# TXPAFV2.net
KiCad netlist of a schematic drawn in Altium Designer
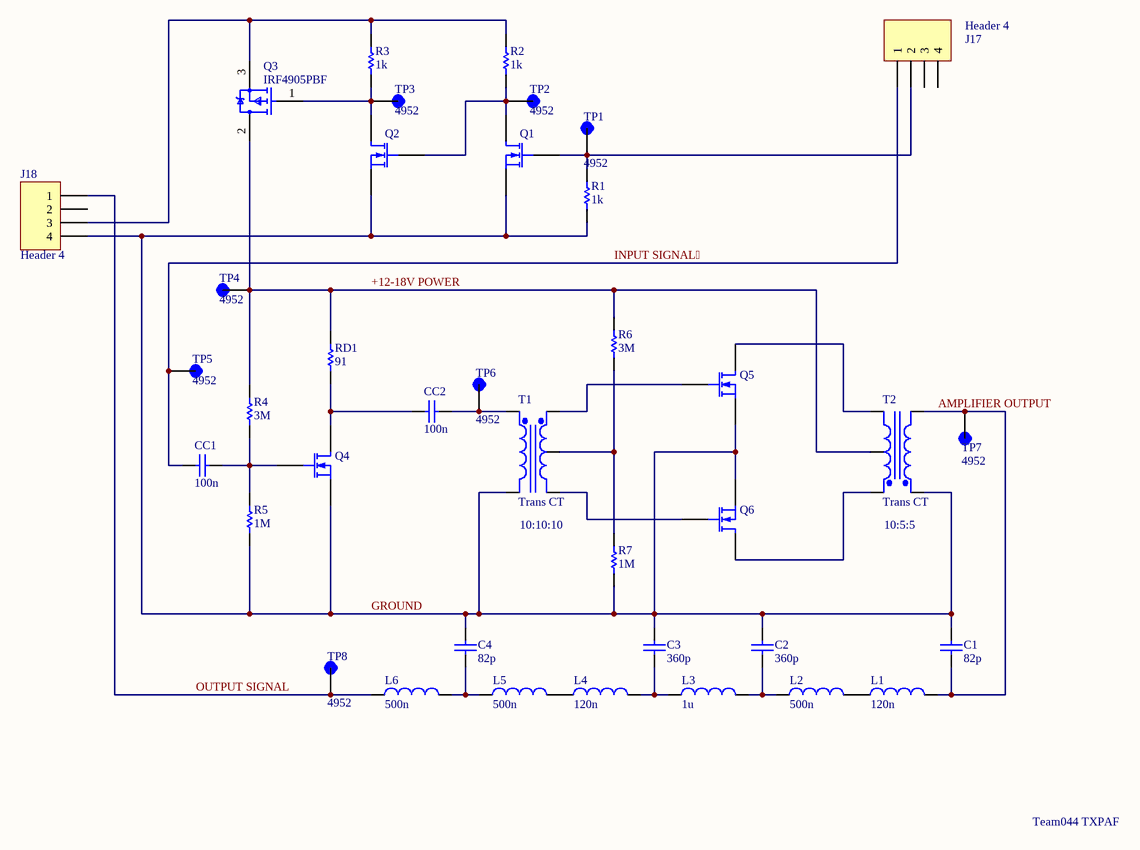
[diagram p0: TXPAFV2.SchDoc]

(export (version "E")
  (design (tool "Eeschema 10.0.6"))
  (components
    (comp (ref "C1")
      (value "82p")
      (footprint "K820J15C0GF5TL2")
      (description "Capacitor")
      (libsource (lib "Simulation Generic Components") (part "Capacitor"))
    )
    (comp (ref "C2")
      (value "360p")
      (footprint "C322C361J5G5TA")
      (description "Capacitor")
      (libsource (lib "Simulation Generic Components") (part "Capacitor"))
    )
    (comp (ref "C3")
      (value "360p")
      (footprint "C322C361J5G5TA")
      (description "Capacitor")
      (libsource (lib "Simulation Generic Components") (part "Capacitor"))
    )
    (comp (ref "C4")
      (value "82p")
      (footprint "K820J15C0GF5TL2")
      (description "Capacitor")
      (libsource (lib "Simulation Generic Components") (part "Capacitor"))
    )
    (comp (ref "CC1")
      (value "100n")
      (footprint "K104K15X7RF5TL2")
      (description "Capacitor")
      (libsource (lib "Simulation Generic Components") (part "Capacitor"))
    )
    (comp (ref "CC2")
      (value "100n")
      (footprint "K104K15X7RF5TL2")
      (description "Capacitor")
      (libsource (lib "Simulation Generic Components") (part "Capacitor"))
    )
    (comp (ref "J17")
      (value "Header 4")
      (footprint "HDR1X4")
      (description "Header, 4-Pin")
      (fields (field (name "PUBLISHER") "Altium Limited"))
      (libsource (lib "") (part "Header 4_1"))
    )
    (comp (ref "J18")
      (value "Header 4")
      (footprint "HDR1X4")
      (description "Header, 4-Pin")
      (fields (field (name "PUBLISHER") "Altium Limited"))
      (libsource (lib "Miscellaneous Connectors") (part "Header 4"))
    )
    (comp (ref "L1")
      (value "120n")
      (footprint "9230-96-RC")
      (description "Inductor")
      (libsource (lib "Simulation Generic Components") (part "Inductor"))
    )
    (comp (ref "L2")
      (value "500n")
      (footprint "78432010005")
      (description "Inductor")
      (libsource (lib "Simulation Generic Components") (part "Inductor"))
    )
    (comp (ref "L3")
      (value "1u")
      (footprint "9250A-102-RC")
      (description "Inductor")
      (libsource (lib "Simulation Generic Components") (part "Inductor"))
    )
    (comp (ref "L4")
      (value "120n")
      (footprint "9230-96-RC")
      (description "Inductor")
      (libsource (lib "Simulation Generic Components") (part "Inductor"))
    )
    (comp (ref "L5")
      (value "500n")
      (footprint "78432010005")
      (description "Inductor")
      (libsource (lib "Simulation Generic Components") (part "Inductor"))
    )
    (comp (ref "L6")
      (value "500n")
      (footprint "78432010005")
      (description "Inductor")
      (libsource (lib "Simulation Generic Components") (part "Inductor"))
    )
    (comp (ref "Q1")
      (value "N-chanel Power MOSFET VDMOS Model")
      (footprint "BS170")
      (libsource (lib "Simulation Generic Components") (part "MOSFET N-ch VDMOS"))
    )
    (comp (ref "Q2")
      (value "N-chanel Power MOSFET VDMOS Model")
      (footprint "BS170")
      (libsource (lib "Simulation Generic Components") (part "MOSFET N-ch VDMOS"))
    )
    (comp (ref "Q3")
      (value "IRF4905PBF")
      (footprint "FP-PG-TO220-3-MFG")
      (description "MOSFET P-CH 55V 74A TO-220AB")
      (libsource (lib "Altium Content Vault") (part "7c43f5ccbd0f8ca8bbf61673af0f16f"))
    )
    (comp (ref "Q4")
      (value "N-chanel Power MOSFET VDMOS Model")
      (footprint "BS170")
      (libsource (lib "Simulation Generic Components") (part "MOSFET N-ch VDMOS"))
    )
    (comp (ref "Q5")
      (value "N-chanel Power MOSFET VDMOS Model")
      (footprint "BS170")
      (libsource (lib "Simulation Generic Components") (part "MOSFET N-ch VDMOS"))
    )
    (comp (ref "Q6")
      (value "N-chanel Power MOSFET VDMOS Model")
      (footprint "BS170")
      (libsource (lib "Simulation Generic Components") (part "MOSFET N-ch VDMOS"))
    )
    (comp (ref "R1")
      (value "1k")
      (footprint "CF14JT1K00")
      (description "Resistor")
      (libsource (lib "Simulation Generic Components") (part "Resistor"))
    )
    (comp (ref "R2")
      (value "1k")
      (footprint "CF14JT1K00")
      (description "Resistor")
      (libsource (lib "Simulation Generic Components") (part "Resistor"))
    )
    (comp (ref "R3")
      (value "1k")
      (footprint "CF14JT1K00")
      (description "Resistor")
      (libsource (lib "Simulation Generic Components") (part "Resistor"))
    )
    (comp (ref "R4")
      (value "3M")
      (footprint "HVR3700003004FR500")
      (description "Resistor")
      (libsource (lib "Simulation Generic Components") (part "Resistor"))
    )
    (comp (ref "R5")
      (value "1M")
      (footprint "MBB0207VD1004BC100")
      (description "Resistor")
      (libsource (lib "Simulation Generic Components") (part "Resistor"))
    )
    (comp (ref "R6")
      (value "3M")
      (footprint "HVR3700003004FR500")
      (description "Resistor")
      (libsource (lib "Simulation Generic Components") (part "Resistor"))
    )
    (comp (ref "R7")
      (value "1M")
      (footprint "MBB0207VD1004BC100")
      (description "Resistor")
      (libsource (lib "Simulation Generic Components") (part "Resistor"))
    )
    (comp (ref "RD1")
      (value "91")
      (footprint "RR02J91RTB")
      (description "Resistor")
      (libsource (lib "Simulation Generic Components") (part "Resistor"))
    )
    (comp (ref "T1")
      (value "Trans CT")
      (footprint "CT-Transformer")
      (description "Center-Tapped Transformer (Coupled Inductor Model)")
      (fields (field (name "PUBLISHER") "Altium Limited"))
      (libsource (lib "ECE295-Other") (part "Centre-tapped transformer wound on a binocular core"))
    )
    (comp (ref "T2")
      (value "Trans CT")
      (footprint "CT-Transformer")
      (description "Center-Tapped Transformer (Coupled Inductor Model)")
      (fields (field (name "PUBLISHER") "Altium Limited"))
      (libsource (lib "ECE295-Other") (part "Centre-tapped transformer wound on a binocular core"))
    )
    (comp (ref "TP1") (value "4952") (footprint "4952") (libsource (lib "MyLibrary") (part "4952")))
    (comp (ref "TP2") (value "4952") (footprint "4952") (libsource (lib "MyLibrary") (part "4952")))
    (comp (ref "TP3") (value "4952") (footprint "4952") (libsource (lib "MyLibrary") (part "4952")))
    (comp (ref "TP4") (value "4952") (footprint "4952") (libsource (lib "MyLibrary") (part "4952")))
    (comp (ref "TP5") (value "4952") (footprint "4952") (libsource (lib "MyLibrary") (part "4952")))
    (comp (ref "TP6") (value "4952") (footprint "4952") (libsource (lib "MyLibrary") (part "4952")))
    (comp (ref "TP7") (value "4952") (footprint "4952") (libsource (lib "MyLibrary") (part "4952")))
    (comp (ref "TP8") (value "4952") (footprint "4952") (libsource (lib "MyLibrary") (part "4952")))
  )
  (nets
    (net (code "1") (name "/+12-18V POWER") (class "Default")
      (node (ref "Q3") (pin "2") (pinfunction "DRAIN_2") (pintype "passive"))
      (node (ref "R4") (pin "2") (pinfunction "2_2") (pintype "passive"))
      (node (ref "R6") (pin "2") (pinfunction "2_2") (pintype "passive"))
      (node (ref "RD1") (pin "1") (pinfunction "1_1") (pintype "passive"))
      (node (ref "T2") (pin "2") (pinfunction "SecCT_2") (pintype "passive"))
      (node (ref "TP4") (pin "TP") (pinfunction "TP_TP") (pintype "passive"))
    )
    (net (code "2") (name "/AMPLIFIER OUTPUT") (class "Default")
      (node (ref "C1") (pin "1") (pinfunction "1_1") (pintype "passive"))
      (node (ref "L1") (pin "2") (pinfunction "2_2") (pintype "passive"))
      (node (ref "T2") (pin "5") (pinfunction "Pri-_5") (pintype "passive"))
      (node (ref "TP7") (pin "TP") (pinfunction "TP_TP") (pintype "passive"))
    )
    (net (code "3") (name "/GROUND") (class "Default")
      (node (ref "C1") (pin "2") (pinfunction "2_2") (pintype "passive"))
      (node (ref "C2") (pin "2") (pinfunction "2_2") (pintype "passive"))
      (node (ref "C3") (pin "2") (pinfunction "2_2") (pintype "passive"))
      (node (ref "C4") (pin "2") (pinfunction "2_2") (pintype "passive"))
      (node (ref "J18") (pin "4") (pinfunction "4_4") (pintype "passive"))
      (node (ref "Q1") (pin "3") (pinfunction "S_3") (pintype "passive"))
      (node (ref "Q2") (pin "3") (pinfunction "S_3") (pintype "passive"))
      (node (ref "Q4") (pin "3") (pinfunction "S_3") (pintype "passive"))
      (node (ref "Q5") (pin "3") (pinfunction "S_3") (pintype "passive"))
      (node (ref "Q6") (pin "3") (pinfunction "S_3") (pintype "passive"))
      (node (ref "R1") (pin "1") (pinfunction "1_1") (pintype "passive"))
      (node (ref "R5") (pin "1") (pinfunction "1_1") (pintype "passive"))
      (node (ref "R7") (pin "1") (pinfunction "1_1") (pintype "passive"))
      (node (ref "T1") (pin "5") (pinfunction "Pri-_5") (pintype "passive"))
      (node (ref "T2") (pin "4") (pinfunction "Pri+_4") (pintype "passive"))
    )
    (net (code "4") (name "/INPUT SIGNAL") (class "Default")
      (node (ref "CC1") (pin "2") (pinfunction "2_2") (pintype "passive"))
      (node (ref "J17") (pin "1") (pinfunction "1_1") (pintype "passive"))
      (node (ref "TP5") (pin "TP") (pinfunction "TP_TP") (pintype "passive"))
    )
    (net (code "5") (name "/OUTPUT SIGNAL") (class "Default")
      (node (ref "J18") (pin "1") (pinfunction "1_1") (pintype "passive"))
      (node (ref "L6") (pin "1") (pinfunction "1_1") (pintype "passive"))
      (node (ref "TP8") (pin "TP") (pinfunction "TP_TP") (pintype "passive"))
    )
    (net (code "6") (name "Net-(C2-Pad1)") (class "Default")
      (node (ref "C2") (pin "1") (pinfunction "1_1") (pintype "passive"))
      (node (ref "L2") (pin "1") (pinfunction "1_1") (pintype "passive"))
      (node (ref "L3") (pin "2") (pinfunction "2_2") (pintype "passive"))
    )
    (net (code "7") (name "Net-(C3-Pad1)") (class "Default")
      (node (ref "C3") (pin "1") (pinfunction "1_1") (pintype "passive"))
      (node (ref "L3") (pin "1") (pinfunction "1_1") (pintype "passive"))
      (node (ref "L4") (pin "2") (pinfunction "2_2") (pintype "passive"))
    )
    (net (code "8") (name "Net-(C4-Pad1)") (class "Default")
      (node (ref "C4") (pin "1") (pinfunction "1_1") (pintype "passive"))
      (node (ref "L5") (pin "1") (pinfunction "1_1") (pintype "passive"))
      (node (ref "L6") (pin "2") (pinfunction "2_2") (pintype "passive"))
    )
    (net (code "9") (name "Net-(L1-Pad1)") (class "Default")
      (node (ref "L1") (pin "1") (pinfunction "1_1") (pintype "passive"))
      (node (ref "L2") (pin "2") (pinfunction "2_2") (pintype "passive"))
    )
    (net (code "10") (name "Net-(L4-Pad1)") (class "Default")
      (node (ref "L4") (pin "1") (pinfunction "1_1") (pintype "passive"))
      (node (ref "L5") (pin "2") (pinfunction "2_2") (pintype "passive"))
    )
    (net (code "11") (name "Net-(Q1-D)") (class "Default")
      (node (ref "Q1") (pin "1") (pinfunction "D_1") (pintype "passive"))
      (node (ref "Q2") (pin "2") (pinfunction "G_2") (pintype "passive"))
      (node (ref "R2") (pin "1") (pinfunction "1_1") (pintype "passive"))
      (node (ref "TP2") (pin "TP") (pinfunction "TP_TP") (pintype "passive"))
    )
    (net (code "12") (name "Net-(Q1-G)") (class "Default")
      (node (ref "J17") (pin "2") (pinfunction "2_2") (pintype "passive"))
      (node (ref "Q1") (pin "2") (pinfunction "G_2") (pintype "passive"))
      (node (ref "R1") (pin "2") (pinfunction "2_2") (pintype "passive"))
      (node (ref "TP1") (pin "TP") (pinfunction "TP_TP") (pintype "passive"))
    )
    (net (code "13") (name "Net-(Q2-D)") (class "Default")
      (node (ref "Q2") (pin "1") (pinfunction "D_1") (pintype "passive"))
      (node (ref "Q3") (pin "1") (pinfunction "GATE_1") (pintype "passive"))
      (node (ref "R3") (pin "1") (pinfunction "1_1") (pintype "passive"))
      (node (ref "TP3") (pin "TP") (pinfunction "TP_TP") (pintype "passive"))
    )
    (net (code "14") (name "Net-(Q3-SOURCE)") (class "Default")
      (node (ref "J18") (pin "3") (pinfunction "3_3") (pintype "passive"))
      (node (ref "Q3") (pin "3") (pinfunction "SOURCE_3") (pintype "passive"))
      (node (ref "R2") (pin "2") (pinfunction "2_2") (pintype "passive"))
      (node (ref "R3") (pin "2") (pinfunction "2_2") (pintype "passive"))
    )
    (net (code "15") (name "Net-(Q4-D)") (class "Default")
      (node (ref "CC2") (pin "2") (pinfunction "2_2") (pintype "passive"))
      (node (ref "Q4") (pin "1") (pinfunction "D_1") (pintype "passive"))
      (node (ref "RD1") (pin "2") (pinfunction "2_2") (pintype "passive"))
    )
    (net (code "16") (name "Net-(Q4-G)") (class "Default")
      (node (ref "CC1") (pin "1") (pinfunction "1_1") (pintype "passive"))
      (node (ref "Q4") (pin "2") (pinfunction "G_2") (pintype "passive"))
      (node (ref "R4") (pin "1") (pinfunction "1_1") (pintype "passive"))
      (node (ref "R5") (pin "2") (pinfunction "2_2") (pintype "passive"))
    )
    (net (code "17") (name "Net-(Q5-D)") (class "Default")
      (node (ref "Q5") (pin "1") (pinfunction "D_1") (pintype "passive"))
      (node (ref "T2") (pin "3") (pinfunction "Sec-_3") (pintype "passive"))
    )
    (net (code "18") (name "Net-(Q5-G)") (class "Default")
      (node (ref "Q5") (pin "2") (pinfunction "G_2") (pintype "passive"))
      (node (ref "T1") (pin "1") (pinfunction "Sec+_1") (pintype "passive"))
    )
    (net (code "19") (name "Net-(Q6-D)") (class "Default")
      (node (ref "Q6") (pin "1") (pinfunction "D_1") (pintype "passive"))
      (node (ref "T2") (pin "1") (pinfunction "Sec+_1") (pintype "passive"))
    )
    (net (code "20") (name "Net-(Q6-G)") (class "Default")
      (node (ref "Q6") (pin "2") (pinfunction "G_2") (pintype "passive"))
      (node (ref "T1") (pin "3") (pinfunction "Sec-_3") (pintype "passive"))
    )
    (net (code "21") (name "Net-(T1-Pri+)") (class "Default")
      (node (ref "CC2") (pin "1") (pinfunction "1_1") (pintype "passive"))
      (node (ref "T1") (pin "4") (pinfunction "Pri+_4") (pintype "passive"))
      (node (ref "TP6") (pin "TP") (pinfunction "TP_TP") (pintype "passive"))
    )
    (net (code "22") (name "Net-(T1-SecCT)") (class "Default")
      (node (ref "R6") (pin "1") (pinfunction "1_1") (pintype "passive"))
      (node (ref "R7") (pin "2") (pinfunction "2_2") (pintype "passive"))
      (node (ref "T1") (pin "2") (pinfunction "SecCT_2") (pintype "passive"))
    )
    (net (code "23") (name "unconnected-(J17-Pad3)") (class "Default")
      (node (ref "J17") (pin "3") (pinfunction "3_3") (pintype "passive"))
    )
    (net (code "24") (name "unconnected-(J17-Pad4)") (class "Default")
      (node (ref "J17") (pin "4") (pinfunction "4_4") (pintype "passive"))
    )
    (net (code "25") (name "unconnected-(J18-Pad2)") (class "Default")
      (node (ref "J18") (pin "2") (pinfunction "2_2") (pintype "passive"))
    )
  )
)
